# untitled.net
KiCad netlist of a schematic drawn in EAGLE
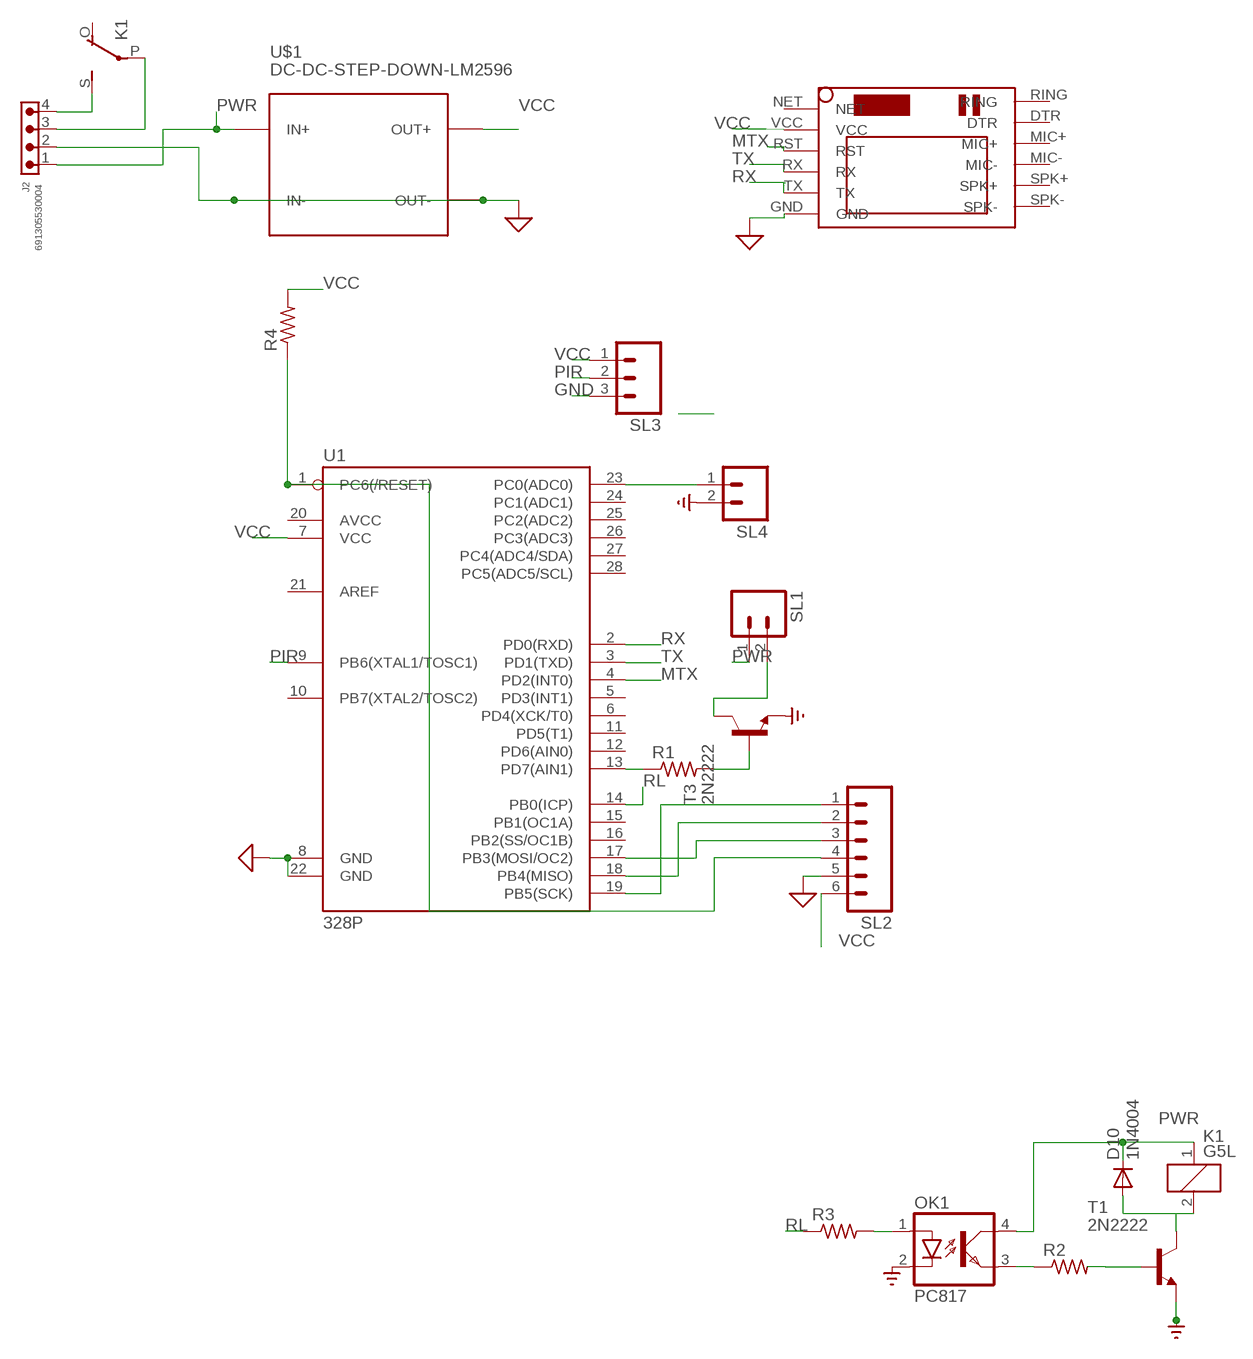
[diagram p0: schematic, sheet 1]

(export (version "E")
  (design (tool "Eeschema 10.0.6"))
  (components
    (comp (ref "D10")
      (value "1N4004")
      (footprint "eagle-import:DO41-10")
      (libsource (lib "eagle-import") (part "1N4004"))
    )
    (comp (ref "J2")
      (value "691305530004")
      (footprint "eagle-import:691305530004")
      (libsource (lib "eagle-import") (part "691305530004"))
    )
    (comp (ref "K1")
      (value "G5L")
      (footprint "eagle-import:G5LE")
      (libsource (lib "eagle-import") (part "G5L"))
    )
    (comp (ref "OK1")
      (value "PC817")
      (footprint "eagle-import:DIL04")
      (fields (field (name "MPN") "PC817X4J000F"))
      (libsource (lib "eagle-import") (part "PC817"))
    )
    (comp (ref "R1")
      (value "R-US_0207/10")
      (footprint "eagle-import:0207_10")
      (libsource (lib "eagle-import") (part "R-US_0207/10"))
    )
    (comp (ref "R2")
      (value "R-US_0207/10")
      (footprint "eagle-import:0207_10")
      (libsource (lib "eagle-import") (part "R-US_0207/10"))
    )
    (comp (ref "R3")
      (value "R-US_0207/15")
      (footprint "eagle-import:0207_15")
      (libsource (lib "eagle-import") (part "adafruit_420_R-US_0207/15"))
    )
    (comp (ref "R4")
      (value "R-US_0207/15")
      (footprint "eagle-import:0207_15")
      (libsource (lib "eagle-import") (part "R-US_0207/15"))
    )
    (comp (ref "SL1")
      (value "M02")
      (footprint "eagle-import:02P")
      (libsource (lib "eagle-import") (part "M02"))
    )
    (comp (ref "SL2")
      (value "M06")
      (footprint "eagle-import:06P")
      (libsource (lib "eagle-import") (part "M06"))
    )
    (comp (ref "SL3")
      (value "M03")
      (footprint "eagle-import:03P")
      (libsource (lib "eagle-import") (part "M03"))
    )
    (comp (ref "SL4")
      (value "M02")
      (footprint "eagle-import:02P")
      (libsource (lib "eagle-import") (part "M02"))
    )
    (comp (ref "T1")
      (value "2N2222")
      (footprint "eagle-import:TO92-EBC-OVAL")
      (libsource (lib "eagle-import") (part "2N2222"))
    )
    (comp (ref "T3")
      (value "2N2222")
      (footprint "eagle-import:TO92-EBC-OVAL")
      (libsource (lib "eagle-import") (part "2N2222"))
    )
    (comp (ref "U$1")
      (value "DC-DC-STEP-DOWN-LM2596")
      (footprint "eagle-import:DC-DC-STEP-DOWN-LM2596")
      (libsource (lib "eagle-import") (part "DC-DC-STEP-DOWN-LM2596"))
    )
    (comp (ref "U$2")
      (value "SIM800LMODULE")
      (footprint "eagle-import:SIM800LMODULE")
      (libsource (lib "eagle-import") (part "SIM800LMODULE"))
    )
    (comp (ref "U1")
      (value "328P")
      (footprint "eagle-import:DIP28")
      (libsource (lib "eagle-import") (part "ATMEGA328P_PDIP"))
    )
  )
  (nets
    (net (code "1") (name "/MTX") (class "Default")
      (node (ref "U$2") (pin "RST") (pinfunction "RST_RST") (pintype "bidirectional"))
      (node (ref "U1") (pin "4") (pinfunction "PD2(INT0)_4") (pintype "bidirectional"))
    )
    (net (code "2") (name "/PIR") (class "Default")
      (node (ref "SL3") (pin "2") (pinfunction "2_2") (pintype "passive"))
      (node (ref "U1") (pin "9") (pinfunction "PB6(XTAL1/TOSC1)_9") (pintype "bidirectional"))
    )
    (net (code "3") (name "/PWR") (class "Default")
      (node (ref "D10") (pin "C") (pinfunction "C_C") (pintype "passive"))
      (node (ref "J2") (pin "1") (pinfunction "1_1") (pintype "passive"))
      (node (ref "K1") (pin "1") (pinfunction "1_1") (pintype "passive"))
      (node (ref "OK1") (pin "4") (pinfunction "COL_4") (pintype "passive"))
      (node (ref "SL1") (pin "1") (pinfunction "1_1") (pintype "passive"))
      (node (ref "U$1") (pin "IN+") (pinfunction "IN+_IN+") (pintype "bidirectional"))
    )
    (net (code "4") (name "/RL") (class "Default")
      (node (ref "R3") (pin "1") (pinfunction "1_1") (pintype "passive"))
      (node (ref "U1") (pin "14") (pinfunction "PB0(ICP)_14") (pintype "bidirectional"))
    )
    (net (code "5") (name "/RX") (class "Default")
      (node (ref "U$2") (pin "TX") (pinfunction "TX_TX") (pintype "bidirectional"))
      (node (ref "U1") (pin "2") (pinfunction "PD0(RXD)_2") (pintype "bidirectional"))
    )
    (net (code "6") (name "/TX") (class "Default")
      (node (ref "U$2") (pin "RX") (pinfunction "RX_RX") (pintype "bidirectional"))
      (node (ref "U1") (pin "3") (pinfunction "PD1(TXD)_3") (pintype "bidirectional"))
    )
    (net (code "7") (name "/VCC") (class "Default")
      (node (ref "R4") (pin "2") (pinfunction "2_2") (pintype "passive"))
      (node (ref "SL2") (pin "6") (pinfunction "6_6") (pintype "passive"))
      (node (ref "SL3") (pin "1") (pinfunction "1_1") (pintype "passive"))
      (node (ref "U$1") (pin "OUT+") (pinfunction "OUT+_OUT+") (pintype "bidirectional"))
      (node (ref "U$2") (pin "VCC") (pinfunction "VCC_VCC") (pintype "bidirectional"))
      (node (ref "U1") (pin "7") (pinfunction "VCC_7") (pintype "bidirectional"))
    )
    (net (code "8") (name "Net-(D10-PadA)") (class "Default")
      (node (ref "D10") (pin "A") (pinfunction "A_A") (pintype "passive"))
      (node (ref "K1") (pin "2") (pinfunction "2_2") (pintype "passive"))
      (node (ref "T1") (pin "C") (pinfunction "C_C") (pintype "passive"))
    )
    (net (code "9") (name "Net-(J2-Pad3)") (class "Default")
      (node (ref "J2") (pin "3") (pinfunction "3_3") (pintype "passive"))
      (node (ref "K1") (pin "P") (pinfunction "P_P") (pintype "passive"))
    )
    (net (code "10") (name "Net-(J2-Pad4)") (class "Default")
      (node (ref "J2") (pin "4") (pinfunction "4_4") (pintype "passive"))
      (node (ref "K1") (pin "S") (pinfunction "S_S") (pintype "passive"))
    )
    (net (code "11") (name "Net-(OK1-A)") (class "Default")
      (node (ref "OK1") (pin "1") (pinfunction "A_1") (pintype "passive"))
      (node (ref "R3") (pin "2") (pinfunction "2_2") (pintype "passive"))
    )
    (net (code "12") (name "Net-(OK1-EMIT)") (class "Default")
      (node (ref "OK1") (pin "3") (pinfunction "EMIT_3") (pintype "passive"))
      (node (ref "R2") (pin "1") (pinfunction "1_1") (pintype "passive"))
    )
    (net (code "13") (name "Net-(R1-Pad2)") (class "Default")
      (node (ref "R1") (pin "2") (pinfunction "2_2") (pintype "passive"))
      (node (ref "T3") (pin "B") (pinfunction "B_B") (pintype "passive"))
    )
    (net (code "14") (name "Net-(R2-Pad2)") (class "Default")
      (node (ref "R2") (pin "2") (pinfunction "2_2") (pintype "passive"))
      (node (ref "T1") (pin "B") (pinfunction "B_B") (pintype "passive"))
    )
    (net (code "15") (name "Net-(SL1-Pad2)") (class "Default")
      (node (ref "SL1") (pin "2") (pinfunction "2_2") (pintype "passive"))
      (node (ref "T3") (pin "C") (pinfunction "C_C") (pintype "passive"))
    )
    (net (code "16") (name "Net-(U1-PB3(MOSI{slash}OC2))") (class "Default")
      (node (ref "SL2") (pin "3") (pinfunction "3_3") (pintype "passive"))
      (node (ref "U1") (pin "17") (pinfunction "PB3(MOSI/OC2)_17") (pintype "bidirectional"))
    )
    (net (code "17") (name "Net-(U1-PB4(MISO))") (class "Default")
      (node (ref "SL2") (pin "2") (pinfunction "2_2") (pintype "passive"))
      (node (ref "U1") (pin "18") (pinfunction "PB4(MISO)_18") (pintype "bidirectional"))
    )
    (net (code "18") (name "Net-(U1-PB5(SCK))") (class "Default")
      (node (ref "SL2") (pin "1") (pinfunction "1_1") (pintype "passive"))
      (node (ref "U1") (pin "19") (pinfunction "PB5(SCK)_19") (pintype "bidirectional"))
    )
    (net (code "19") (name "Net-(U1-PC0(ADC0))") (class "Default")
      (node (ref "SL4") (pin "1") (pinfunction "1_1") (pintype "passive"))
      (node (ref "U1") (pin "23") (pinfunction "PC0(ADC0)_23") (pintype "bidirectional"))
    )
    (net (code "20") (name "Net-(U1-PC6({slash}RESET))") (class "Default")
      (node (ref "R4") (pin "1") (pinfunction "1_1") (pintype "passive"))
      (node (ref "SL2") (pin "4") (pinfunction "4_4") (pintype "passive"))
      (node (ref "U1") (pin "1") (pinfunction "PC6(/RESET)_1") (pintype "bidirectional"))
    )
    (net (code "21") (name "Net-(U1-PD7(AIN1))") (class "Default")
      (node (ref "R1") (pin "1") (pinfunction "1_1") (pintype "passive"))
      (node (ref "U1") (pin "13") (pinfunction "PD7(AIN1)_13") (pintype "bidirectional"))
    )
    (net (code "22") (name "SUP") (class "Default")
      (node (ref "J2") (pin "2") (pinfunction "2_2") (pintype "passive"))
      (node (ref "OK1") (pin "2") (pinfunction "C_2") (pintype "passive"))
      (node (ref "SL2") (pin "5") (pinfunction "5_5") (pintype "passive"))
      (node (ref "SL3") (pin "3") (pinfunction "3_3") (pintype "passive"))
      (node (ref "SL4") (pin "2") (pinfunction "2_2") (pintype "passive"))
      (node (ref "T1") (pin "E") (pinfunction "E_E") (pintype "passive"))
      (node (ref "T3") (pin "E") (pinfunction "E_E") (pintype "passive"))
      (node (ref "U$1") (pin "IN-") (pinfunction "IN-_IN-") (pintype "bidirectional"))
      (node (ref "U$1") (pin "OUT-") (pinfunction "OUT-_OUT-") (pintype "bidirectional"))
      (node (ref "U$2") (pin "GND") (pinfunction "GND_GND") (pintype "bidirectional"))
      (node (ref "U1") (pin "22") (pinfunction "GND_22") (pintype "bidirectional"))
      (node (ref "U1") (pin "8") (pinfunction "GND_8") (pintype "bidirectional"))
    )
    (net (code "23") (name "unconnected-(K1-PadO)") (class "Default")
      (node (ref "K1") (pin "O") (pinfunction "O_O") (pintype "passive"))
    )
    (net (code "24") (name "unconnected-(U$2-PadDTR)") (class "Default")
      (node (ref "U$2") (pin "DTR") (pinfunction "DTR_DTR") (pintype "bidirectional"))
    )
    (net (code "25") (name "unconnected-(U$2-PadMIC+)") (class "Default")
      (node (ref "U$2") (pin "MIC+") (pinfunction "MIC+_MIC+") (pintype "bidirectional"))
    )
    (net (code "26") (name "unconnected-(U$2-PadMIC-)") (class "Default")
      (node (ref "U$2") (pin "MIC-") (pinfunction "MIC-_MIC-") (pintype "bidirectional"))
    )
    (net (code "27") (name "unconnected-(U$2-PadNET)") (class "Default")
      (node (ref "U$2") (pin "NET") (pinfunction "NET_NET") (pintype "bidirectional"))
    )
    (net (code "28") (name "unconnected-(U$2-PadRING)") (class "Default")
      (node (ref "U$2") (pin "RING") (pinfunction "RING_RING") (pintype "bidirectional"))
    )
    (net (code "29") (name "unconnected-(U$2-PadSPK+)") (class "Default")
      (node (ref "U$2") (pin "SPK+") (pinfunction "SPK+_SPK+") (pintype "bidirectional"))
    )
    (net (code "30") (name "unconnected-(U$2-PadSPK-)") (class "Default")
      (node (ref "U$2") (pin "SPK-") (pinfunction "SPK-_SPK-") (pintype "bidirectional"))
    )
    (net (code "31") (name "unconnected-(U1-AREF-Pad21)") (class "Default")
      (node (ref "U1") (pin "21") (pinfunction "AREF_21") (pintype "bidirectional"))
    )
    (net (code "32") (name "unconnected-(U1-AVCC-Pad20)") (class "Default")
      (node (ref "U1") (pin "20") (pinfunction "AVCC_20") (pintype "bidirectional"))
    )
    (net (code "33") (name "unconnected-(U1-PB1(OC1A)-Pad15)") (class "Default")
      (node (ref "U1") (pin "15") (pinfunction "PB1(OC1A)_15") (pintype "bidirectional"))
    )
    (net (code "34") (name "unconnected-(U1-PB2(SS{slash}OC1B)-Pad16)") (class "Default")
      (node (ref "U1") (pin "16") (pinfunction "PB2(SS/OC1B)_16") (pintype "bidirectional"))
    )
    (net (code "35") (name "unconnected-(U1-PB7(XTAL2{slash}TOSC2)-Pad10)") (class "Default")
      (node (ref "U1") (pin "10") (pinfunction "PB7(XTAL2/TOSC2)_10") (pintype "bidirectional"))
    )
    (net (code "36") (name "unconnected-(U1-PC1(ADC1)-Pad24)") (class "Default")
      (node (ref "U1") (pin "24") (pinfunction "PC1(ADC1)_24") (pintype "bidirectional"))
    )
    (net (code "37") (name "unconnected-(U1-PC2(ADC2)-Pad25)") (class "Default")
      (node (ref "U1") (pin "25") (pinfunction "PC2(ADC2)_25") (pintype "bidirectional"))
    )
    (net (code "38") (name "unconnected-(U1-PC3(ADC3)-Pad26)") (class "Default")
      (node (ref "U1") (pin "26") (pinfunction "PC3(ADC3)_26") (pintype "bidirectional"))
    )
    (net (code "39") (name "unconnected-(U1-PC4(ADC4{slash}SDA)-Pad27)") (class "Default")
      (node (ref "U1") (pin "27") (pinfunction "PC4(ADC4/SDA)_27") (pintype "bidirectional"))
    )
    (net (code "40") (name "unconnected-(U1-PC5(ADC5{slash}SCL)-Pad28)") (class "Default")
      (node (ref "U1") (pin "28") (pinfunction "PC5(ADC5/SCL)_28") (pintype "bidirectional"))
    )
    (net (code "41") (name "unconnected-(U1-PD3(INT1)-Pad5)") (class "Default")
      (node (ref "U1") (pin "5") (pinfunction "PD3(INT1)_5") (pintype "bidirectional"))
    )
    (net (code "42") (name "unconnected-(U1-PD4(XCK{slash}T0)-Pad6)") (class "Default")
      (node (ref "U1") (pin "6") (pinfunction "PD4(XCK/T0)_6") (pintype "bidirectional"))
    )
    (net (code "43") (name "unconnected-(U1-PD5(T1)-Pad11)") (class "Default")
      (node (ref "U1") (pin "11") (pinfunction "PD5(T1)_11") (pintype "bidirectional"))
    )
    (net (code "44") (name "unconnected-(U1-PD6(AIN0)-Pad12)") (class "Default")
      (node (ref "U1") (pin "12") (pinfunction "PD6(AIN0)_12") (pintype "bidirectional"))
    )
  )
)
